# Manual_Final_1_2.net
KiCad netlist of a schematic drawn in EAGLE
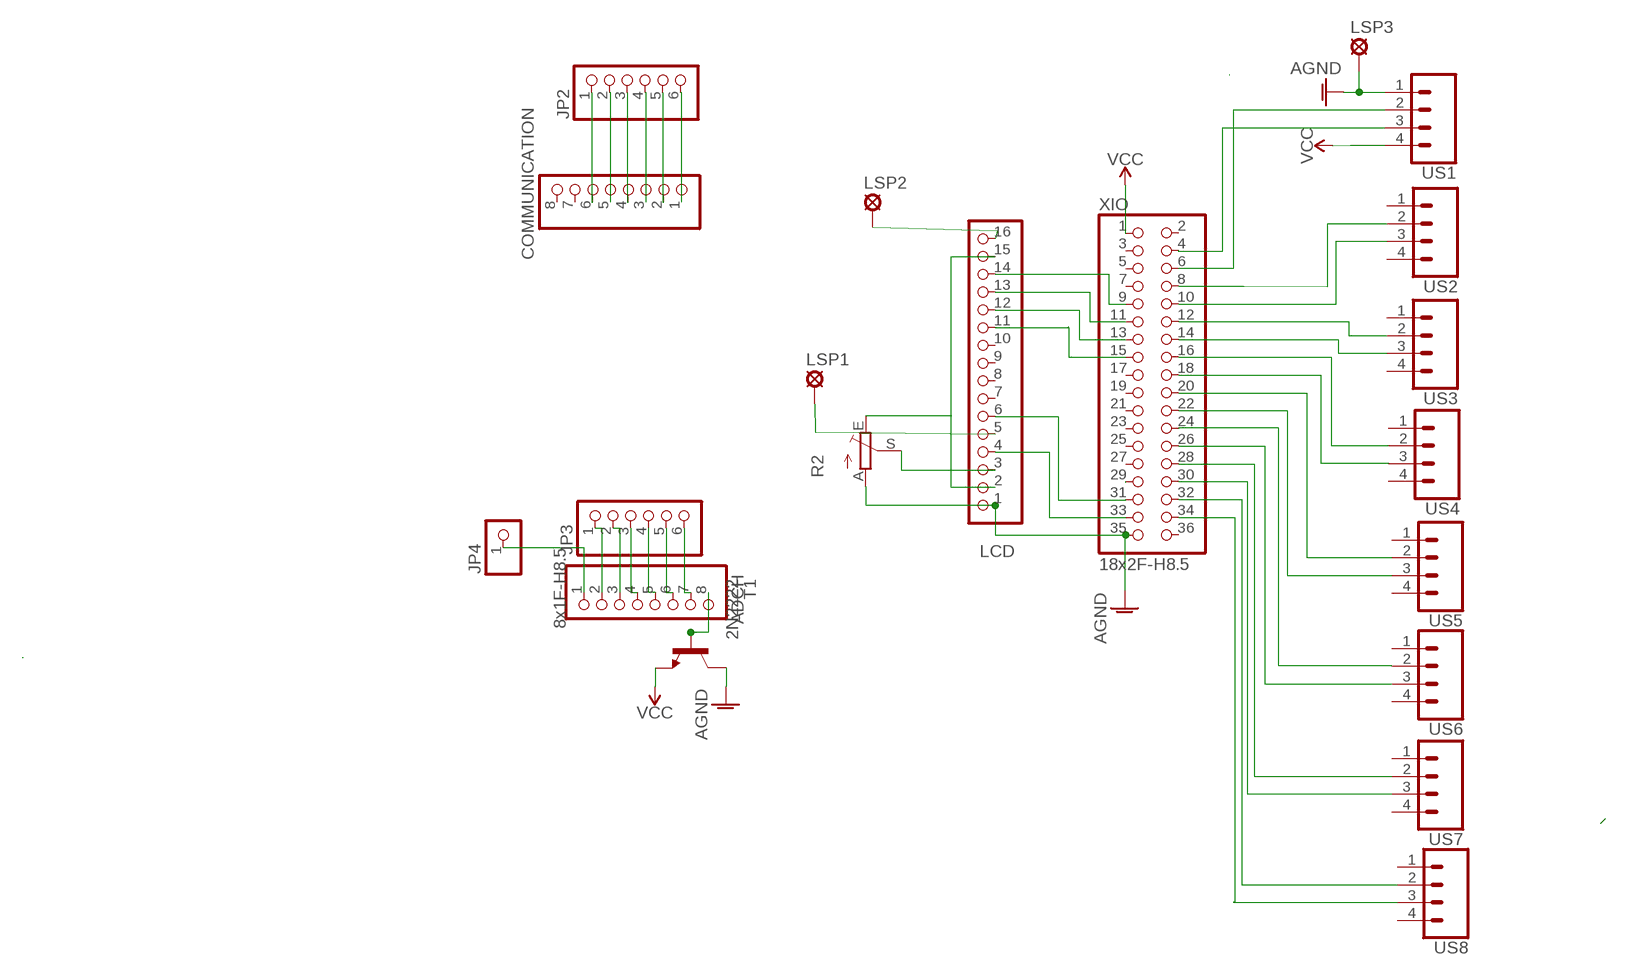
[diagram p0: schematic, sheet 1]

(export (version "E")
  (design (tool "Eeschema 10.0.6"))
  (components
    (comp (ref "ADCH")
      (value "8x1F-H8.5")
      (footprint "eagle-import:1X08")
      (libsource (lib "eagle-import") (part "PINHD-1X8"))
    )
    (comp (ref "COMMUNICATION")
      (value "8x1F-H8.5")
      (footprint "eagle-import:1X08")
      (libsource (lib "eagle-import") (part "PINHD-1X8"))
    )
    (comp (ref "JP2")
      (value "PINHD-1X6")
      (footprint "eagle-import:1X06")
      (libsource (lib "eagle-import") (part "PINHD-1X6"))
    )
    (comp (ref "JP3")
      (value "PINHD-1X6")
      (footprint "eagle-import:1X06")
      (libsource (lib "eagle-import") (part "PINHD-1X6"))
    )
    (comp (ref "JP4")
      (value "PINHD-1X1")
      (footprint "eagle-import:1X01")
      (libsource (lib "eagle-import") (part "PINHD-1X1"))
    )
    (comp (ref "LCD")
      (value "PINHD-1X16")
      (footprint "eagle-import:1X16")
      (libsource (lib "eagle-import") (part "PINHD-1X16"))
    )
    (comp (ref "LSP1")
      (value "SE14")
      (footprint "eagle-import:SE14")
      (libsource (lib "eagle-import") (part "SE14"))
    )
    (comp (ref "LSP2")
      (value "SE14")
      (footprint "eagle-import:SE14")
      (libsource (lib "eagle-import") (part "SE14"))
    )
    (comp (ref "LSP3")
      (value "SE14")
      (footprint "eagle-import:SE14")
      (libsource (lib "eagle-import") (part "SE14"))
    )
    (comp (ref "R2")
      (value "TRIM_EU-RS3")
      (footprint "eagle-import:RS3")
      (libsource (lib "eagle-import") (part "TRIM_EU-RS3"))
    )
    (comp (ref "T1")
      (value "2N2222")
      (footprint "eagle-import:TO92-EBC-OVAL")
      (libsource (lib "eagle-import") (part "2N2222"))
    )
    (comp (ref "US1")
      (value "CONN_04LOCK_LONGPADS")
      (footprint "eagle-import:1X04_LOCK_LONGPADS")
      (libsource (lib "eagle-import") (part "CONN_04LOCK_LONGPADS"))
    )
    (comp (ref "US2")
      (value "CONN_04LOCK_LONGPADS")
      (footprint "eagle-import:1X04_LOCK_LONGPADS")
      (libsource (lib "eagle-import") (part "CONN_04LOCK_LONGPADS"))
    )
    (comp (ref "US3")
      (value "CONN_04LOCK_LONGPADS")
      (footprint "eagle-import:1X04_LOCK_LONGPADS")
      (libsource (lib "eagle-import") (part "CONN_04LOCK_LONGPADS"))
    )
    (comp (ref "US4")
      (value "CONN_04LOCK_LONGPADS")
      (footprint "eagle-import:1X04_LOCK_LONGPADS")
      (libsource (lib "eagle-import") (part "CONN_04LOCK_LONGPADS"))
    )
    (comp (ref "US5")
      (value "CONN_04LOCK_LONGPADS")
      (footprint "eagle-import:1X04_LOCK_LONGPADS")
      (libsource (lib "eagle-import") (part "CONN_04LOCK_LONGPADS"))
    )
    (comp (ref "US6")
      (value "CONN_04LOCK_LONGPADS")
      (footprint "eagle-import:1X04_LOCK_LONGPADS")
      (libsource (lib "eagle-import") (part "CONN_04LOCK_LONGPADS"))
    )
    (comp (ref "US7")
      (value "CONN_04LOCK_LONGPADS")
      (footprint "eagle-import:1X04_LOCK_LONGPADS")
      (libsource (lib "eagle-import") (part "CONN_04LOCK_LONGPADS"))
    )
    (comp (ref "US8")
      (value "CONN_04LOCK_LONGPADS")
      (footprint "eagle-import:1X04_LOCK_LONGPADS")
      (libsource (lib "eagle-import") (part "CONN_04LOCK_LONGPADS"))
    )
    (comp (ref "XIO")
      (value "18x2F-H8.5")
      (footprint "eagle-import:2X18")
      (libsource (lib "eagle-import") (part "PINHD-2X18"))
    )
  )
  (nets
    (net (code "1") (name "AGND") (class "Default")
      (node (ref "LCD") (pin "1") (pinfunction "1_1") (pintype "passive"))
      (node (ref "LSP3") (pin "MP") (pinfunction "MP_MP") (pintype "passive"))
      (node (ref "R2") (pin "A") (pinfunction "A_A") (pintype "passive"))
      (node (ref "T1") (pin "C") (pinfunction "C_C") (pintype "passive"))
      (node (ref "US1") (pin "1") (pinfunction "1_1") (pintype "passive"))
      (node (ref "XIO") (pin "35") (pinfunction "35_35") (pintype "passive"))
    )
    (net (code "2") (name "Net-(ADCH-Pad1)") (class "Default")
      (node (ref "ADCH") (pin "1") (pinfunction "1_1") (pintype "passive"))
      (node (ref "JP4") (pin "1") (pinfunction "1_1") (pintype "passive"))
    )
    (net (code "3") (name "Net-(ADCH-Pad2)") (class "Default")
      (node (ref "ADCH") (pin "2") (pinfunction "2_2") (pintype "passive"))
      (node (ref "JP3") (pin "1") (pinfunction "1_1") (pintype "passive"))
    )
    (net (code "4") (name "Net-(ADCH-Pad3)") (class "Default")
      (node (ref "ADCH") (pin "3") (pinfunction "3_3") (pintype "passive"))
      (node (ref "JP3") (pin "2") (pinfunction "2_2") (pintype "passive"))
    )
    (net (code "5") (name "Net-(ADCH-Pad4)") (class "Default")
      (node (ref "ADCH") (pin "4") (pinfunction "4_4") (pintype "passive"))
      (node (ref "JP3") (pin "3") (pinfunction "3_3") (pintype "passive"))
    )
    (net (code "6") (name "Net-(ADCH-Pad5)") (class "Default")
      (node (ref "ADCH") (pin "5") (pinfunction "5_5") (pintype "passive"))
      (node (ref "JP3") (pin "4") (pinfunction "4_4") (pintype "passive"))
    )
    (net (code "7") (name "Net-(ADCH-Pad6)") (class "Default")
      (node (ref "ADCH") (pin "6") (pinfunction "6_6") (pintype "passive"))
      (node (ref "JP3") (pin "5") (pinfunction "5_5") (pintype "passive"))
    )
    (net (code "8") (name "Net-(ADCH-Pad7)") (class "Default")
      (node (ref "ADCH") (pin "7") (pinfunction "7_7") (pintype "passive"))
      (node (ref "JP3") (pin "6") (pinfunction "6_6") (pintype "passive"))
    )
    (net (code "9") (name "Net-(ADCH-Pad8)") (class "Default")
      (node (ref "ADCH") (pin "8") (pinfunction "8_8") (pintype "passive"))
      (node (ref "T1") (pin "B") (pinfunction "B_B") (pintype "passive"))
    )
    (net (code "10") (name "Net-(COMMUNICATION-Pad1)") (class "Default")
      (node (ref "COMMUNICATION") (pin "1") (pinfunction "1_1") (pintype "passive"))
      (node (ref "JP2") (pin "6") (pinfunction "6_6") (pintype "passive"))
    )
    (net (code "11") (name "Net-(COMMUNICATION-Pad2)") (class "Default")
      (node (ref "COMMUNICATION") (pin "2") (pinfunction "2_2") (pintype "passive"))
      (node (ref "JP2") (pin "5") (pinfunction "5_5") (pintype "passive"))
    )
    (net (code "12") (name "Net-(COMMUNICATION-Pad3)") (class "Default")
      (node (ref "COMMUNICATION") (pin "3") (pinfunction "3_3") (pintype "passive"))
      (node (ref "JP2") (pin "4") (pinfunction "4_4") (pintype "passive"))
    )
    (net (code "13") (name "Net-(COMMUNICATION-Pad4)") (class "Default")
      (node (ref "COMMUNICATION") (pin "4") (pinfunction "4_4") (pintype "passive"))
      (node (ref "JP2") (pin "3") (pinfunction "3_3") (pintype "passive"))
    )
    (net (code "14") (name "Net-(COMMUNICATION-Pad5)") (class "Default")
      (node (ref "COMMUNICATION") (pin "5") (pinfunction "5_5") (pintype "passive"))
      (node (ref "JP2") (pin "2") (pinfunction "2_2") (pintype "passive"))
    )
    (net (code "15") (name "Net-(COMMUNICATION-Pad6)") (class "Default")
      (node (ref "COMMUNICATION") (pin "6") (pinfunction "6_6") (pintype "passive"))
      (node (ref "JP2") (pin "1") (pinfunction "1_1") (pintype "passive"))
    )
    (net (code "16") (name "Net-(LCD-Pad3)") (class "Default")
      (node (ref "LCD") (pin "3") (pinfunction "3_3") (pintype "passive"))
      (node (ref "R2") (pin "S") (pinfunction "S_S") (pintype "passive"))
    )
    (net (code "17") (name "Net-(LCD-Pad4)") (class "Default")
      (node (ref "LCD") (pin "4") (pinfunction "4_4") (pintype "passive"))
      (node (ref "XIO") (pin "33") (pinfunction "33_33") (pintype "passive"))
    )
    (net (code "18") (name "Net-(LCD-Pad5)") (class "Default")
      (node (ref "LCD") (pin "5") (pinfunction "5_5") (pintype "passive"))
      (node (ref "LSP1") (pin "MP") (pinfunction "MP_MP") (pintype "passive"))
    )
    (net (code "19") (name "Net-(LCD-Pad6)") (class "Default")
      (node (ref "LCD") (pin "6") (pinfunction "6_6") (pintype "passive"))
      (node (ref "XIO") (pin "31") (pinfunction "31_31") (pintype "passive"))
    )
    (net (code "20") (name "Net-(LCD-Pad11)") (class "Default")
      (node (ref "LCD") (pin "11") (pinfunction "11_11") (pintype "passive"))
      (node (ref "XIO") (pin "15") (pinfunction "15_15") (pintype "passive"))
    )
    (net (code "21") (name "Net-(LCD-Pad12)") (class "Default")
      (node (ref "LCD") (pin "12") (pinfunction "12_12") (pintype "passive"))
      (node (ref "XIO") (pin "13") (pinfunction "13_13") (pintype "passive"))
    )
    (net (code "22") (name "Net-(LCD-Pad13)") (class "Default")
      (node (ref "LCD") (pin "13") (pinfunction "13_13") (pintype "passive"))
      (node (ref "XIO") (pin "11") (pinfunction "11_11") (pintype "passive"))
    )
    (net (code "23") (name "Net-(LCD-Pad14)") (class "Default")
      (node (ref "LCD") (pin "14") (pinfunction "14_14") (pintype "passive"))
      (node (ref "XIO") (pin "9") (pinfunction "9_9") (pintype "passive"))
    )
    (net (code "24") (name "Net-(LCD-Pad15)") (class "Default")
      (node (ref "LCD") (pin "15") (pinfunction "15_15") (pintype "passive"))
      (node (ref "LCD") (pin "2") (pinfunction "2_2") (pintype "passive"))
      (node (ref "R2") (pin "E") (pinfunction "E_E") (pintype "passive"))
    )
    (net (code "25") (name "Net-(LCD-Pad16)") (class "Default")
      (node (ref "LCD") (pin "16") (pinfunction "16_16") (pintype "passive"))
      (node (ref "LSP2") (pin "MP") (pinfunction "MP_MP") (pintype "passive"))
    )
    (net (code "26") (name "Net-(US1-Pad2)") (class "Default")
      (node (ref "US1") (pin "2") (pinfunction "2_2") (pintype "passive"))
      (node (ref "XIO") (pin "6") (pinfunction "6_6") (pintype "passive"))
    )
    (net (code "27") (name "Net-(US1-Pad3)") (class "Default")
      (node (ref "US1") (pin "3") (pinfunction "3_3") (pintype "passive"))
      (node (ref "XIO") (pin "4") (pinfunction "4_4") (pintype "passive"))
    )
    (net (code "28") (name "Net-(US2-Pad2)") (class "Default")
      (node (ref "US2") (pin "2") (pinfunction "2_2") (pintype "passive"))
      (node (ref "XIO") (pin "8") (pinfunction "8_8") (pintype "passive"))
    )
    (net (code "29") (name "Net-(US2-Pad3)") (class "Default")
      (node (ref "US2") (pin "3") (pinfunction "3_3") (pintype "passive"))
      (node (ref "XIO") (pin "10") (pinfunction "10_10") (pintype "passive"))
    )
    (net (code "30") (name "Net-(US3-Pad2)") (class "Default")
      (node (ref "US3") (pin "2") (pinfunction "2_2") (pintype "passive"))
      (node (ref "XIO") (pin "12") (pinfunction "12_12") (pintype "passive"))
    )
    (net (code "31") (name "Net-(US3-Pad3)") (class "Default")
      (node (ref "US3") (pin "3") (pinfunction "3_3") (pintype "passive"))
      (node (ref "XIO") (pin "14") (pinfunction "14_14") (pintype "passive"))
    )
    (net (code "32") (name "Net-(US4-Pad2)") (class "Default")
      (node (ref "US4") (pin "2") (pinfunction "2_2") (pintype "passive"))
      (node (ref "XIO") (pin "16") (pinfunction "16_16") (pintype "passive"))
    )
    (net (code "33") (name "Net-(US4-Pad3)") (class "Default")
      (node (ref "US4") (pin "3") (pinfunction "3_3") (pintype "passive"))
      (node (ref "XIO") (pin "18") (pinfunction "18_18") (pintype "passive"))
    )
    (net (code "34") (name "Net-(US5-Pad2)") (class "Default")
      (node (ref "US5") (pin "2") (pinfunction "2_2") (pintype "passive"))
      (node (ref "XIO") (pin "20") (pinfunction "20_20") (pintype "passive"))
    )
    (net (code "35") (name "Net-(US5-Pad3)") (class "Default")
      (node (ref "US5") (pin "3") (pinfunction "3_3") (pintype "passive"))
      (node (ref "XIO") (pin "22") (pinfunction "22_22") (pintype "passive"))
    )
    (net (code "36") (name "Net-(US6-Pad2)") (class "Default")
      (node (ref "US6") (pin "2") (pinfunction "2_2") (pintype "passive"))
      (node (ref "XIO") (pin "24") (pinfunction "24_24") (pintype "passive"))
    )
    (net (code "37") (name "Net-(US6-Pad3)") (class "Default")
      (node (ref "US6") (pin "3") (pinfunction "3_3") (pintype "passive"))
      (node (ref "XIO") (pin "26") (pinfunction "26_26") (pintype "passive"))
    )
    (net (code "38") (name "Net-(US7-Pad2)") (class "Default")
      (node (ref "US7") (pin "2") (pinfunction "2_2") (pintype "passive"))
      (node (ref "XIO") (pin "28") (pinfunction "28_28") (pintype "passive"))
    )
    (net (code "39") (name "Net-(US7-Pad3)") (class "Default")
      (node (ref "US7") (pin "3") (pinfunction "3_3") (pintype "passive"))
      (node (ref "XIO") (pin "30") (pinfunction "30_30") (pintype "passive"))
    )
    (net (code "40") (name "Net-(US8-Pad2)") (class "Default")
      (node (ref "US8") (pin "2") (pinfunction "2_2") (pintype "passive"))
      (node (ref "XIO") (pin "32") (pinfunction "32_32") (pintype "passive"))
    )
    (net (code "41") (name "Net-(US8-Pad3)") (class "Default")
      (node (ref "US8") (pin "3") (pinfunction "3_3") (pintype "passive"))
      (node (ref "XIO") (pin "34") (pinfunction "34_34") (pintype "passive"))
    )
    (net (code "42") (name "VCC") (class "Default")
      (node (ref "T1") (pin "E") (pinfunction "E_E") (pintype "passive"))
      (node (ref "US1") (pin "4") (pinfunction "4_4") (pintype "passive"))
      (node (ref "XIO") (pin "1") (pinfunction "1_1") (pintype "passive"))
    )
    (net (code "43") (name "unconnected-(COMMUNICATION-Pad7)") (class "Default")
      (node (ref "COMMUNICATION") (pin "7") (pinfunction "7_7") (pintype "passive"))
    )
    (net (code "44") (name "unconnected-(COMMUNICATION-Pad8)") (class "Default")
      (node (ref "COMMUNICATION") (pin "8") (pinfunction "8_8") (pintype "passive"))
    )
    (net (code "45") (name "unconnected-(LCD-Pad7)") (class "Default")
      (node (ref "LCD") (pin "7") (pinfunction "7_7") (pintype "passive"))
    )
    (net (code "46") (name "unconnected-(LCD-Pad8)") (class "Default")
      (node (ref "LCD") (pin "8") (pinfunction "8_8") (pintype "passive"))
    )
    (net (code "47") (name "unconnected-(LCD-Pad9)") (class "Default")
      (node (ref "LCD") (pin "9") (pinfunction "9_9") (pintype "passive"))
    )
    (net (code "48") (name "unconnected-(LCD-Pad10)") (class "Default")
      (node (ref "LCD") (pin "10") (pinfunction "10_10") (pintype "passive"))
    )
    (net (code "49") (name "unconnected-(US2-Pad1)") (class "Default")
      (node (ref "US2") (pin "1") (pinfunction "1_1") (pintype "passive"))
    )
    (net (code "50") (name "unconnected-(US2-Pad4)") (class "Default")
      (node (ref "US2") (pin "4") (pinfunction "4_4") (pintype "passive"))
    )
    (net (code "51") (name "unconnected-(US3-Pad1)") (class "Default")
      (node (ref "US3") (pin "1") (pinfunction "1_1") (pintype "passive"))
    )
    (net (code "52") (name "unconnected-(US3-Pad4)") (class "Default")
      (node (ref "US3") (pin "4") (pinfunction "4_4") (pintype "passive"))
    )
    (net (code "53") (name "unconnected-(US4-Pad1)") (class "Default")
      (node (ref "US4") (pin "1") (pinfunction "1_1") (pintype "passive"))
    )
    (net (code "54") (name "unconnected-(US4-Pad4)") (class "Default")
      (node (ref "US4") (pin "4") (pinfunction "4_4") (pintype "passive"))
    )
    (net (code "55") (name "unconnected-(US5-Pad1)") (class "Default")
      (node (ref "US5") (pin "1") (pinfunction "1_1") (pintype "passive"))
    )
    (net (code "56") (name "unconnected-(US5-Pad4)") (class "Default")
      (node (ref "US5") (pin "4") (pinfunction "4_4") (pintype "passive"))
    )
    (net (code "57") (name "unconnected-(US6-Pad1)") (class "Default")
      (node (ref "US6") (pin "1") (pinfunction "1_1") (pintype "passive"))
    )
    (net (code "58") (name "unconnected-(US6-Pad4)") (class "Default")
      (node (ref "US6") (pin "4") (pinfunction "4_4") (pintype "passive"))
    )
    (net (code "59") (name "unconnected-(US7-Pad1)") (class "Default")
      (node (ref "US7") (pin "1") (pinfunction "1_1") (pintype "passive"))
    )
    (net (code "60") (name "unconnected-(US7-Pad4)") (class "Default")
      (node (ref "US7") (pin "4") (pinfunction "4_4") (pintype "passive"))
    )
    (net (code "61") (name "unconnected-(US8-Pad1)") (class "Default")
      (node (ref "US8") (pin "1") (pinfunction "1_1") (pintype "passive"))
    )
    (net (code "62") (name "unconnected-(US8-Pad4)") (class "Default")
      (node (ref "US8") (pin "4") (pinfunction "4_4") (pintype "passive"))
    )
    (net (code "63") (name "unconnected-(XIO-Pad2)") (class "Default")
      (node (ref "XIO") (pin "2") (pinfunction "2_2") (pintype "passive"))
    )
    (net (code "64") (name "unconnected-(XIO-Pad3)") (class "Default")
      (node (ref "XIO") (pin "3") (pinfunction "3_3") (pintype "passive"))
    )
    (net (code "65") (name "unconnected-(XIO-Pad5)") (class "Default")
      (node (ref "XIO") (pin "5") (pinfunction "5_5") (pintype "passive"))
    )
    (net (code "66") (name "unconnected-(XIO-Pad7)") (class "Default")
      (node (ref "XIO") (pin "7") (pinfunction "7_7") (pintype "passive"))
    )
    (net (code "67") (name "unconnected-(XIO-Pad17)") (class "Default")
      (node (ref "XIO") (pin "17") (pinfunction "17_17") (pintype "passive"))
    )
    (net (code "68") (name "unconnected-(XIO-Pad19)") (class "Default")
      (node (ref "XIO") (pin "19") (pinfunction "19_19") (pintype "passive"))
    )
    (net (code "69") (name "unconnected-(XIO-Pad21)") (class "Default")
      (node (ref "XIO") (pin "21") (pinfunction "21_21") (pintype "passive"))
    )
    (net (code "70") (name "unconnected-(XIO-Pad23)") (class "Default")
      (node (ref "XIO") (pin "23") (pinfunction "23_23") (pintype "passive"))
    )
    (net (code "71") (name "unconnected-(XIO-Pad25)") (class "Default")
      (node (ref "XIO") (pin "25") (pinfunction "25_25") (pintype "passive"))
    )
    (net (code "72") (name "unconnected-(XIO-Pad27)") (class "Default")
      (node (ref "XIO") (pin "27") (pinfunction "27_27") (pintype "passive"))
    )
    (net (code "73") (name "unconnected-(XIO-Pad29)") (class "Default")
      (node (ref "XIO") (pin "29") (pinfunction "29_29") (pintype "passive"))
    )
    (net (code "74") (name "unconnected-(XIO-Pad36)") (class "Default")
      (node (ref "XIO") (pin "36") (pinfunction "36_36") (pintype "passive"))
    )
  )
)
